# design.net
KiCad netlist of a schematic drawn in EAGLE
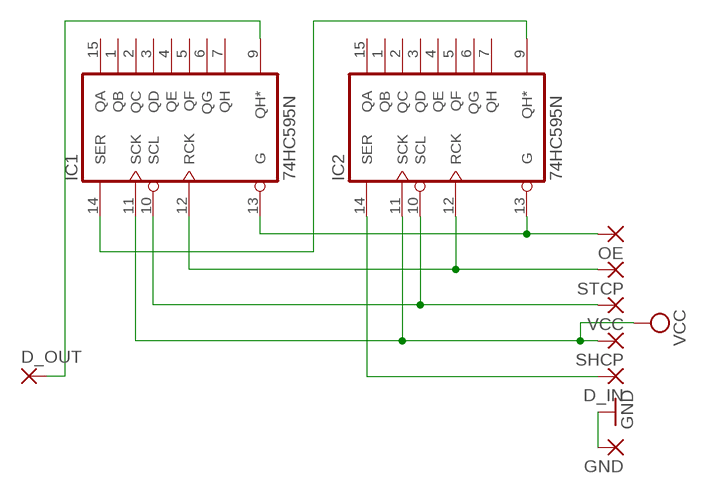
[diagram p0: schematic, sheet 1]

(export (version "E")
  (design (tool "Eeschema 10.0.6"))
  (components
    (comp (ref "D_IN")
      (value "1,6/0,8")
      (footprint "eagle-import:1,6_0,8")
      (libsource (lib "eagle-import") (part "1,6/0,8"))
    )
    (comp (ref "D_OUT")
      (value "1,6/0,8")
      (footprint "eagle-import:1,6_0,8")
      (libsource (lib "eagle-import") (part "1,6/0,8"))
    )
    (comp (ref "GND")
      (value "1,6/0,8")
      (footprint "eagle-import:1,6_0,8")
      (libsource (lib "eagle-import") (part "1,6/0,8"))
    )
    (comp (ref "IC1")
      (value "74HC595N")
      (footprint "eagle-import:DIL16")
      (libsource (lib "eagle-import") (part "74595NHC"))
    )
    (comp (ref "IC2")
      (value "74HC595N")
      (footprint "eagle-import:DIL16")
      (libsource (lib "eagle-import") (part "74595NHC"))
    )
    (comp (ref "OE")
      (value "1,6/0,8")
      (footprint "eagle-import:1,6_0,8")
      (libsource (lib "eagle-import") (part "1,6/0,8"))
    )
    (comp (ref "SHCP")
      (value "1,6/0,8")
      (footprint "eagle-import:1,6_0,8")
      (libsource (lib "eagle-import") (part "1,6/0,8"))
    )
    (comp (ref "STCP")
      (value "1,6/0,8")
      (footprint "eagle-import:1,6_0,8")
      (libsource (lib "eagle-import") (part "1,6/0,8"))
    )
    (comp (ref "VCC")
      (value "1,6/0,8")
      (footprint "eagle-import:1,6_0,8")
      (libsource (lib "eagle-import") (part "1,6/0,8"))
    )
  )
  (nets
    (net (code "1") (name "GND") (class "Default")
      (node (ref "GND") (pin "1") (pinfunction "P_1") (pintype "passive"))
    )
    (net (code "2") (name "Net-(D_IN-P)") (class "Default")
      (node (ref "D_IN") (pin "1") (pinfunction "P_1") (pintype "passive"))
      (node (ref "IC2") (pin "14") (pinfunction "SER_14") (pintype "input"))
    )
    (net (code "3") (name "Net-(D_OUT-P)") (class "Default")
      (node (ref "D_OUT") (pin "1") (pinfunction "P_1") (pintype "passive"))
      (node (ref "IC1") (pin "9") (pinfunction "QH*_9") (pintype "tri_state"))
    )
    (net (code "4") (name "Net-(IC1A-G)") (class "Default")
      (node (ref "IC1") (pin "13") (pinfunction "G_13") (pintype "input"))
      (node (ref "IC2") (pin "13") (pinfunction "G_13") (pintype "input"))
      (node (ref "OE") (pin "1") (pinfunction "P_1") (pintype "passive"))
    )
    (net (code "5") (name "Net-(IC1A-RCK)") (class "Default")
      (node (ref "IC1") (pin "12") (pinfunction "RCK_12") (pintype "input"))
      (node (ref "IC2") (pin "12") (pinfunction "RCK_12") (pintype "input"))
      (node (ref "STCP") (pin "1") (pinfunction "P_1") (pintype "passive"))
    )
    (net (code "6") (name "Net-(IC1A-SCL)") (class "Default")
      (node (ref "IC1") (pin "10") (pinfunction "SCL_10") (pintype "input"))
      (node (ref "IC2") (pin "10") (pinfunction "SCL_10") (pintype "input"))
      (node (ref "VCC") (pin "1") (pinfunction "P_1") (pintype "passive"))
    )
    (net (code "7") (name "Net-(IC1A-SER)") (class "Default")
      (node (ref "IC1") (pin "14") (pinfunction "SER_14") (pintype "input"))
      (node (ref "IC2") (pin "9") (pinfunction "QH*_9") (pintype "tri_state"))
    )
    (net (code "8") (name "VCC") (class "Default")
      (node (ref "IC1") (pin "11") (pinfunction "SCK_11") (pintype "input"))
      (node (ref "IC2") (pin "11") (pinfunction "SCK_11") (pintype "input"))
      (node (ref "SHCP") (pin "1") (pinfunction "P_1") (pintype "passive"))
    )
    (net (code "9") (name "unconnected-(IC1A-QA-Pad15)") (class "Default")
      (node (ref "IC1") (pin "15") (pinfunction "QA_15") (pintype "tri_state"))
    )
    (net (code "10") (name "unconnected-(IC1A-QB-Pad1)") (class "Default")
      (node (ref "IC1") (pin "1") (pinfunction "QB_1") (pintype "tri_state"))
    )
    (net (code "11") (name "unconnected-(IC1A-QC-Pad2)") (class "Default")
      (node (ref "IC1") (pin "2") (pinfunction "QC_2") (pintype "tri_state"))
    )
    (net (code "12") (name "unconnected-(IC1A-QD-Pad3)") (class "Default")
      (node (ref "IC1") (pin "3") (pinfunction "QD_3") (pintype "tri_state"))
    )
    (net (code "13") (name "unconnected-(IC1A-QE-Pad4)") (class "Default")
      (node (ref "IC1") (pin "4") (pinfunction "QE_4") (pintype "tri_state"))
    )
    (net (code "14") (name "unconnected-(IC1A-QF-Pad5)") (class "Default")
      (node (ref "IC1") (pin "5") (pinfunction "QF_5") (pintype "tri_state"))
    )
    (net (code "15") (name "unconnected-(IC1A-QG-Pad6)") (class "Default")
      (node (ref "IC1") (pin "6") (pinfunction "QG_6") (pintype "tri_state"))
    )
    (net (code "16") (name "unconnected-(IC1A-QH-Pad7)") (class "Default")
      (node (ref "IC1") (pin "7") (pinfunction "QH_7") (pintype "tri_state"))
    )
    (net (code "17") (name "unconnected-(IC2A-QA-Pad15)") (class "Default")
      (node (ref "IC2") (pin "15") (pinfunction "QA_15") (pintype "tri_state"))
    )
    (net (code "18") (name "unconnected-(IC2A-QB-Pad1)") (class "Default")
      (node (ref "IC2") (pin "1") (pinfunction "QB_1") (pintype "tri_state"))
    )
    (net (code "19") (name "unconnected-(IC2A-QC-Pad2)") (class "Default")
      (node (ref "IC2") (pin "2") (pinfunction "QC_2") (pintype "tri_state"))
    )
    (net (code "20") (name "unconnected-(IC2A-QD-Pad3)") (class "Default")
      (node (ref "IC2") (pin "3") (pinfunction "QD_3") (pintype "tri_state"))
    )
    (net (code "21") (name "unconnected-(IC2A-QE-Pad4)") (class "Default")
      (node (ref "IC2") (pin "4") (pinfunction "QE_4") (pintype "tri_state"))
    )
    (net (code "22") (name "unconnected-(IC2A-QF-Pad5)") (class "Default")
      (node (ref "IC2") (pin "5") (pinfunction "QF_5") (pintype "tri_state"))
    )
    (net (code "23") (name "unconnected-(IC2A-QG-Pad6)") (class "Default")
      (node (ref "IC2") (pin "6") (pinfunction "QG_6") (pintype "tri_state"))
    )
    (net (code "24") (name "unconnected-(IC2A-QH-Pad7)") (class "Default")
      (node (ref "IC2") (pin "7") (pinfunction "QH_7") (pintype "tri_state"))
    )
  )
)
